# Adafruit_Joy_Bonnet.net
KiCad netlist of a schematic drawn in EAGLE
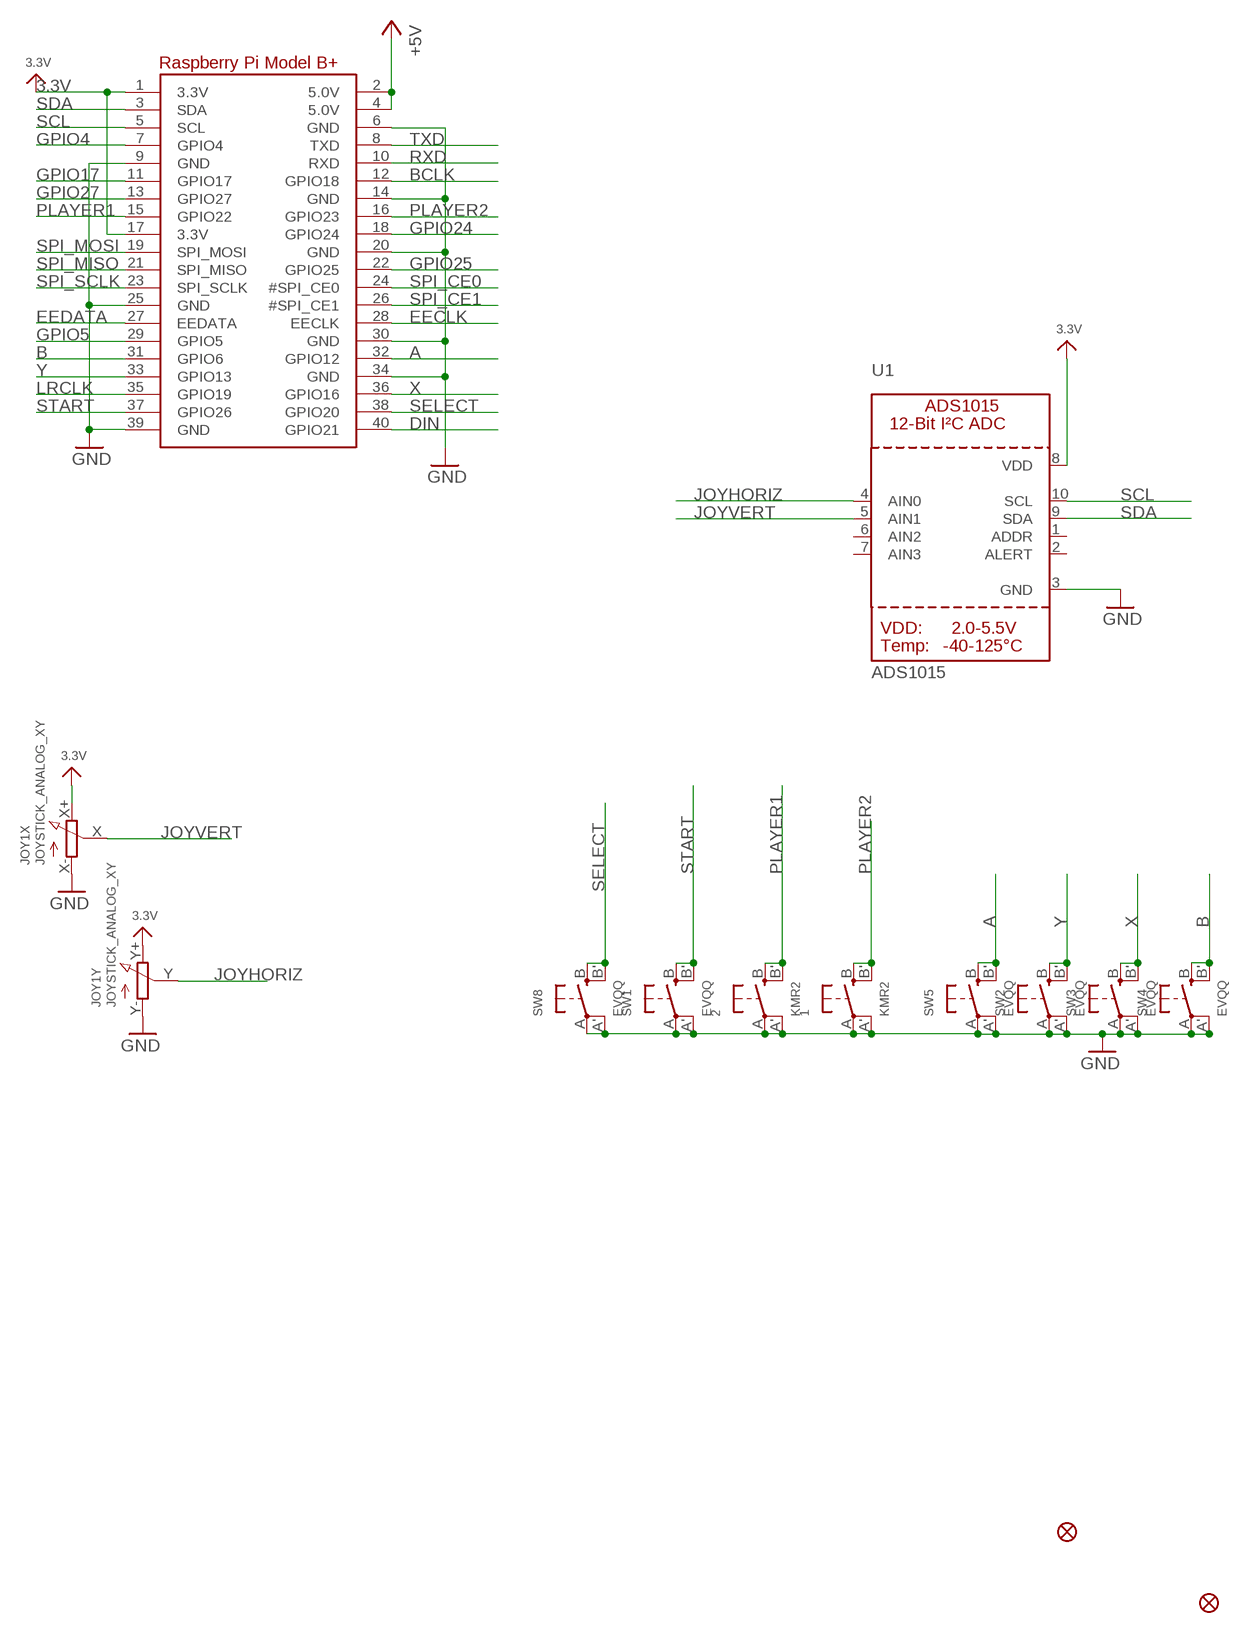
[diagram p0: schematic, sheet 1]

(export (version "E")
  (design (tool "Eeschema 10.0.6"))
  (components
    (comp (ref "1")
      (value "KMR2")
      (footprint "eagle-import:BTN_KMR2_4.6X2.8")
      (libsource (lib "eagle-import") (part "SWITCH_TACT_SMT4.6X2.8"))
    )
    (comp (ref "2")
      (value "KMR2")
      (footprint "eagle-import:BTN_KMR2_4.6X2.8")
      (libsource (lib "eagle-import") (part "SWITCH_TACT_SMT4.6X2.8"))
    )
    (comp (ref "FID2")
      (value "FIDUCIAL_1MM")
      (footprint "eagle-import:FIDUCIAL_1MM")
      (libsource (lib "eagle-import") (part "FIDUCIAL_1MM"))
    )
    (comp (ref "FID3")
      (value "FIDUCIAL_1MM")
      (footprint "eagle-import:FIDUCIAL_1MM")
      (libsource (lib "eagle-import") (part "FIDUCIAL_1MM"))
    )
    (comp (ref "JOY1")
      (value "JOYSTICK_ANALOG_XY")
      (footprint "eagle-import:JOYSTICK_ANALOG_MINITHM")
      (libsource (lib "eagle-import") (part "JOYSTICK_ANALOG_XY"))
    )
    (comp (ref "RPI1")
      (value "RASPBERRYPI_BPLUS_BONNETSMT")
      (footprint "eagle-import:PI_BONNET_SMT")
      (libsource (lib "eagle-import") (part "RASPBERRYPI_BPLUS_BONNETSMT"))
    )
    (comp (ref "SW1")
      (value "EVQQ")
      (footprint "eagle-import:EVQ-Q2_SMALLER")
      (libsource (lib "eagle-import") (part "SWITCH_TACT_SMT_EVQQ2_SMALL"))
    )
    (comp (ref "SW2")
      (value "EVQQ")
      (footprint "eagle-import:EVQ-Q2_SMALLER")
      (libsource (lib "eagle-import") (part "SWITCH_TACT_SMT_EVQQ2_SMALL"))
    )
    (comp (ref "SW3")
      (value "EVQQ")
      (footprint "eagle-import:EVQ-Q2_SMALLER")
      (libsource (lib "eagle-import") (part "SWITCH_TACT_SMT_EVQQ2_SMALL"))
    )
    (comp (ref "SW4")
      (value "EVQQ")
      (footprint "eagle-import:EVQ-Q2_SMALLER")
      (libsource (lib "eagle-import") (part "SWITCH_TACT_SMT_EVQQ2_SMALL"))
    )
    (comp (ref "SW5")
      (value "EVQQ")
      (footprint "eagle-import:EVQ-Q2_SMALLER")
      (libsource (lib "eagle-import") (part "SWITCH_TACT_SMT_EVQQ2_SMALL"))
    )
    (comp (ref "SW8")
      (value "EVQQ")
      (footprint "eagle-import:EVQ-Q2_SMALLER")
      (libsource (lib "eagle-import") (part "SWITCH_TACT_SMT_EVQQ2_SMALL"))
    )
    (comp (ref "U1")
      (value "ADS1015")
      (footprint "eagle-import:MSOP10")
      (libsource (lib "eagle-import") (part "ADC_ADS1015"))
    )
  )
  (nets
    (net (code "1") (name "+5V") (class "Default")
      (node (ref "RPI1") (pin "2") (pinfunction "5.0V_2") (pintype "power_in"))
      (node (ref "RPI1") (pin "4") (pinfunction "5.0V_4") (pintype "power_in"))
    )
    (net (code "2") (name "/A") (class "Default")
      (node (ref "RPI1") (pin "32") (pinfunction "GPIO12_32") (pintype "bidirectional"))
      (node (ref "SW5") (pin "B") (pinfunction "S_B") (pintype "passive"))
      (node (ref "SW5") (pin "B'") (pinfunction "S1_B'") (pintype "passive"))
    )
    (net (code "3") (name "/B") (class "Default")
      (node (ref "RPI1") (pin "31") (pinfunction "GPIO6_31") (pintype "bidirectional"))
      (node (ref "SW4") (pin "B") (pinfunction "S_B") (pintype "passive"))
      (node (ref "SW4") (pin "B'") (pinfunction "S1_B'") (pintype "passive"))
    )
    (net (code "4") (name "/BCLK") (class "Default")
      (node (ref "RPI1") (pin "12") (pinfunction "GPIO18_12") (pintype "bidirectional"))
    )
    (net (code "5") (name "/DIN") (class "Default")
      (node (ref "RPI1") (pin "40") (pinfunction "GPIO21_40") (pintype "bidirectional"))
    )
    (net (code "6") (name "/EECLK") (class "Default")
      (node (ref "RPI1") (pin "28") (pinfunction "EECLK_28") (pintype "bidirectional"))
    )
    (net (code "7") (name "/EEDATA") (class "Default")
      (node (ref "RPI1") (pin "27") (pinfunction "EEDATA_27") (pintype "bidirectional"))
    )
    (net (code "8") (name "/GPIO4") (class "Default")
      (node (ref "RPI1") (pin "7") (pinfunction "GPIO4_7") (pintype "bidirectional"))
    )
    (net (code "9") (name "/GPIO5") (class "Default")
      (node (ref "RPI1") (pin "29") (pinfunction "GPIO5_29") (pintype "bidirectional"))
    )
    (net (code "10") (name "/GPIO17") (class "Default")
      (node (ref "RPI1") (pin "11") (pinfunction "GPIO17_11") (pintype "bidirectional"))
    )
    (net (code "11") (name "/GPIO24") (class "Default")
      (node (ref "RPI1") (pin "18") (pinfunction "GPIO24_18") (pintype "bidirectional"))
    )
    (net (code "12") (name "/GPIO25") (class "Default")
      (node (ref "RPI1") (pin "22") (pinfunction "GPIO25_22") (pintype "bidirectional"))
    )
    (net (code "13") (name "/GPIO27") (class "Default")
      (node (ref "RPI1") (pin "13") (pinfunction "GPIO27_13") (pintype "bidirectional"))
    )
    (net (code "14") (name "/JOYHORIZ") (class "Default")
      (node (ref "JOY1") (pin "Y") (pinfunction "S_Y") (pintype "passive"))
      (node (ref "U1") (pin "4") (pinfunction "AIN0_4") (pintype "bidirectional"))
    )
    (net (code "15") (name "/JOYVERT") (class "Default")
      (node (ref "JOY1") (pin "X") (pinfunction "S_X") (pintype "passive"))
      (node (ref "U1") (pin "5") (pinfunction "AIN1_5") (pintype "bidirectional"))
    )
    (net (code "16") (name "/LRCLK") (class "Default")
      (node (ref "RPI1") (pin "35") (pinfunction "GPIO19_35") (pintype "bidirectional"))
    )
    (net (code "17") (name "/PLAYER1") (class "Default")
      (node (ref "2") (pin "B") (pinfunction "S_B") (pintype "passive"))
      (node (ref "2") (pin "B'") (pinfunction "S1_B'") (pintype "passive"))
      (node (ref "RPI1") (pin "15") (pinfunction "GPIO22_15") (pintype "bidirectional"))
    )
    (net (code "18") (name "/PLAYER2") (class "Default")
      (node (ref "1") (pin "B") (pinfunction "S_B") (pintype "passive"))
      (node (ref "1") (pin "B'") (pinfunction "S1_B'") (pintype "passive"))
      (node (ref "RPI1") (pin "16") (pinfunction "GPIO23_16") (pintype "bidirectional"))
    )
    (net (code "19") (name "/RXD") (class "Default")
      (node (ref "RPI1") (pin "10") (pinfunction "RXD_10") (pintype "bidirectional"))
    )
    (net (code "20") (name "/SCL") (class "Default")
      (node (ref "RPI1") (pin "5") (pinfunction "SCL_5") (pintype "bidirectional"))
      (node (ref "U1") (pin "10") (pinfunction "SCL_10") (pintype "bidirectional"))
    )
    (net (code "21") (name "/SDA") (class "Default")
      (node (ref "RPI1") (pin "3") (pinfunction "SDA_3") (pintype "bidirectional"))
      (node (ref "U1") (pin "9") (pinfunction "SDA_9") (pintype "bidirectional"))
    )
    (net (code "22") (name "/SELECT") (class "Default")
      (node (ref "RPI1") (pin "38") (pinfunction "GPIO20_38") (pintype "bidirectional"))
      (node (ref "SW8") (pin "B") (pinfunction "S_B") (pintype "passive"))
      (node (ref "SW8") (pin "B'") (pinfunction "S1_B'") (pintype "passive"))
    )
    (net (code "23") (name "/SPI_CE0") (class "Default")
      (node (ref "RPI1") (pin "24") (pinfunction "#SPI_CE0_24") (pintype "bidirectional"))
    )
    (net (code "24") (name "/SPI_CE1") (class "Default")
      (node (ref "RPI1") (pin "26") (pinfunction "#SPI_CE1_26") (pintype "bidirectional"))
    )
    (net (code "25") (name "/SPI_MISO") (class "Default")
      (node (ref "RPI1") (pin "21") (pinfunction "SPI_MISO_21") (pintype "bidirectional"))
    )
    (net (code "26") (name "/SPI_MOSI") (class "Default")
      (node (ref "RPI1") (pin "19") (pinfunction "SPI_MOSI_19") (pintype "bidirectional"))
    )
    (net (code "27") (name "/SPI_SCLK") (class "Default")
      (node (ref "RPI1") (pin "23") (pinfunction "SPI_SCLK_23") (pintype "bidirectional"))
    )
    (net (code "28") (name "/START") (class "Default")
      (node (ref "RPI1") (pin "37") (pinfunction "GPIO26_37") (pintype "bidirectional"))
      (node (ref "SW1") (pin "B") (pinfunction "S_B") (pintype "passive"))
      (node (ref "SW1") (pin "B'") (pinfunction "S1_B'") (pintype "passive"))
    )
    (net (code "29") (name "/TXD") (class "Default")
      (node (ref "RPI1") (pin "8") (pinfunction "TXD_8") (pintype "bidirectional"))
    )
    (net (code "30") (name "/X") (class "Default")
      (node (ref "RPI1") (pin "36") (pinfunction "GPIO16_36") (pintype "bidirectional"))
      (node (ref "SW3") (pin "B") (pinfunction "S_B") (pintype "passive"))
      (node (ref "SW3") (pin "B'") (pinfunction "S1_B'") (pintype "passive"))
    )
    (net (code "31") (name "/Y") (class "Default")
      (node (ref "RPI1") (pin "33") (pinfunction "GPIO13_33") (pintype "bidirectional"))
      (node (ref "SW2") (pin "B") (pinfunction "S_B") (pintype "passive"))
      (node (ref "SW2") (pin "B'") (pinfunction "S1_B'") (pintype "passive"))
    )
    (net (code "32") (name "3.3V") (class "Default")
      (node (ref "JOY1") (pin "X+") (pinfunction "E_X+") (pintype "passive"))
      (node (ref "JOY1") (pin "Y+") (pinfunction "E_Y+") (pintype "passive"))
      (node (ref "RPI1") (pin "1") (pinfunction "3.3V_1") (pintype "power_in"))
      (node (ref "RPI1") (pin "17") (pinfunction "3.3V_17") (pintype "power_in"))
      (node (ref "U1") (pin "8") (pinfunction "VDD_8") (pintype "bidirectional"))
    )
    (net (code "33") (name "GND") (class "Default")
      (node (ref "1") (pin "A") (pinfunction "P_A") (pintype "passive"))
      (node (ref "1") (pin "A'") (pinfunction "P1_A'") (pintype "passive"))
      (node (ref "2") (pin "A") (pinfunction "P_A") (pintype "passive"))
      (node (ref "2") (pin "A'") (pinfunction "P1_A'") (pintype "passive"))
      (node (ref "JOY1") (pin "X-") (pinfunction "A_X-") (pintype "passive"))
      (node (ref "JOY1") (pin "Y-") (pinfunction "A_Y-") (pintype "passive"))
      (node (ref "RPI1") (pin "14") (pinfunction "GND_14") (pintype "power_in"))
      (node (ref "RPI1") (pin "20") (pinfunction "GND_20") (pintype "power_in"))
      (node (ref "RPI1") (pin "25") (pinfunction "GND_25") (pintype "power_in"))
      (node (ref "RPI1") (pin "30") (pinfunction "GND_30") (pintype "power_in"))
      (node (ref "RPI1") (pin "34") (pinfunction "GND_34") (pintype "power_in"))
      (node (ref "RPI1") (pin "39") (pinfunction "GND_39") (pintype "power_in"))
      (node (ref "RPI1") (pin "6") (pinfunction "GND_6") (pintype "power_in"))
      (node (ref "RPI1") (pin "9") (pinfunction "GND_9") (pintype "power_in"))
      (node (ref "SW1") (pin "A") (pinfunction "P_A") (pintype "passive"))
      (node (ref "SW1") (pin "A'") (pinfunction "P1_A'") (pintype "passive"))
      (node (ref "SW2") (pin "A") (pinfunction "P_A") (pintype "passive"))
      (node (ref "SW2") (pin "A'") (pinfunction "P1_A'") (pintype "passive"))
      (node (ref "SW3") (pin "A") (pinfunction "P_A") (pintype "passive"))
      (node (ref "SW3") (pin "A'") (pinfunction "P1_A'") (pintype "passive"))
      (node (ref "SW4") (pin "A") (pinfunction "P_A") (pintype "passive"))
      (node (ref "SW4") (pin "A'") (pinfunction "P1_A'") (pintype "passive"))
      (node (ref "SW5") (pin "A") (pinfunction "P_A") (pintype "passive"))
      (node (ref "SW5") (pin "A'") (pinfunction "P1_A'") (pintype "passive"))
      (node (ref "SW8") (pin "A") (pinfunction "P_A") (pintype "passive"))
      (node (ref "SW8") (pin "A'") (pinfunction "P1_A'") (pintype "passive"))
      (node (ref "U1") (pin "3") (pinfunction "GND_3") (pintype "bidirectional"))
    )
    (net (code "34") (name "unconnected-(U1-ADDR-Pad1)") (class "Default")
      (node (ref "U1") (pin "1") (pinfunction "ADDR_1") (pintype "bidirectional"))
    )
    (net (code "35") (name "unconnected-(U1-AIN2-Pad6)") (class "Default")
      (node (ref "U1") (pin "6") (pinfunction "AIN2_6") (pintype "bidirectional"))
    )
    (net (code "36") (name "unconnected-(U1-AIN3-Pad7)") (class "Default")
      (node (ref "U1") (pin "7") (pinfunction "AIN3_7") (pintype "bidirectional"))
    )
    (net (code "37") (name "unconnected-(U1-ALERT-Pad2)") (class "Default")
      (node (ref "U1") (pin "2") (pinfunction "ALERT_2") (pintype "bidirectional"))
    )
  )
)
